# tiny84RGB.net
KiCad netlist of a schematic drawn in EAGLE
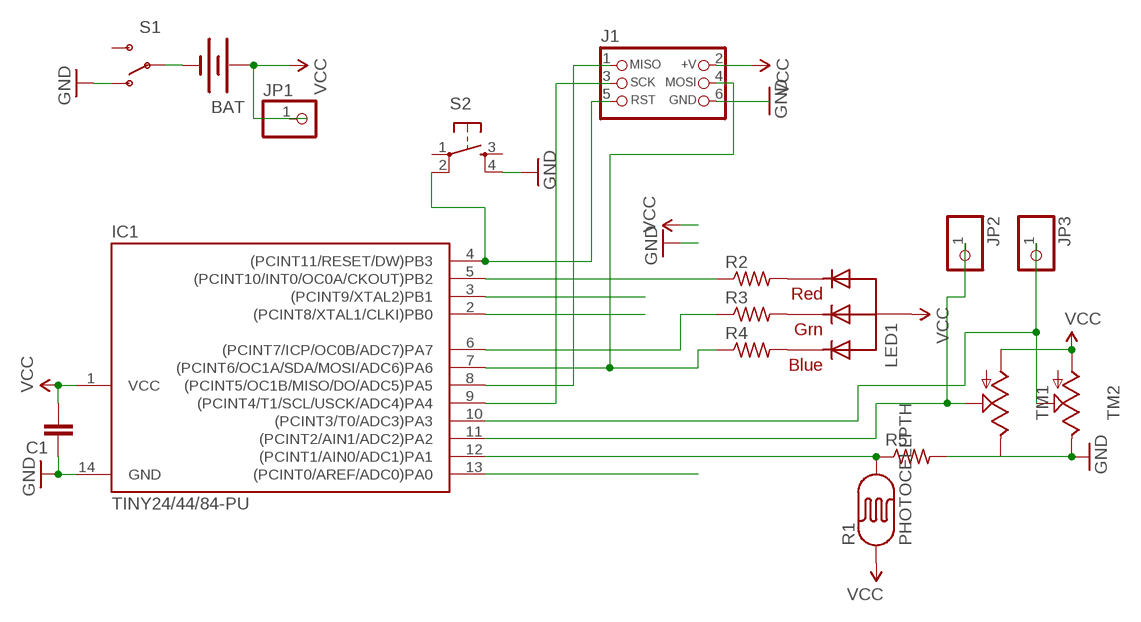
[diagram p0: schematic, sheet 1]

(export (version "E")
  (design (tool "Eeschema 10.0.6"))
  (components
    (comp (ref "BAT")
      (value "BATTERY20PTH")
      (footprint "eagle-import:BATTCOM_20MM_PTH")
      (libsource (lib "eagle-import") (part "BATTERY20PTH"))
    )
    (comp (ref "C1")
      (value "CAPKIT")
      (footprint "eagle-import:CAP-PTH-SMALL-KIT")
      (libsource (lib "eagle-import") (part "CAPKIT"))
    )
    (comp (ref "IC1")
      (value "TINY24/44/84-PU")
      (footprint "eagle-import:DIL14")
      (libsource (lib "eagle-import") (part "TINY24/44/84-PU"))
    )
    (comp (ref "J1")
      (value "CON_HEADER_PRG_AVR_ICSP-PTH")
      (footprint "eagle-import:HEADER_PRG_2X03")
      (libsource (lib "eagle-import") (part "CON_HEADER_PRG_AVR_ICSP-PTH"))
    )
    (comp (ref "JP1")
      (value "PINHD-1X1CB")
      (footprint "eagle-import:1X01-CLEANBIG")
      (libsource (lib "eagle-import") (part "PINHD-1X1CB"))
    )
    (comp (ref "JP2")
      (value "PINHD-1X1CB")
      (footprint "eagle-import:1X01-CLEANBIG")
      (libsource (lib "eagle-import") (part "PINHD-1X1CB"))
    )
    (comp (ref "JP3")
      (value "PINHD-1X1CB")
      (footprint "eagle-import:1X01-CLEANBIG")
      (libsource (lib "eagle-import") (part "PINHD-1X1CB"))
    )
    (comp (ref "LED1")
      (value "RGBLED_CA-5MM")
      (footprint "eagle-import:LED5MMRGB")
      (libsource (lib "eagle-import") (part "RGBLED_CA-5MM"))
    )
    (comp (ref "R1")
      (value "PHOTOCELLPTH")
      (footprint "eagle-import:PHOTOCELL")
      (libsource (lib "eagle-import") (part "PHOTOCELLPTH"))
    )
    (comp (ref "R2")
      (value "R-US_0204/7")
      (footprint "eagle-import:0204_7")
      (libsource (lib "eagle-import") (part "R-US_0204/7"))
    )
    (comp (ref "R3")
      (value "R-US_0204/7")
      (footprint "eagle-import:0204_7")
      (libsource (lib "eagle-import") (part "R-US_0204/7"))
    )
    (comp (ref "R4")
      (value "R-US_0204/7")
      (footprint "eagle-import:0204_7")
      (libsource (lib "eagle-import") (part "R-US_0204/7"))
    )
    (comp (ref "R5")
      (value "R-US_0204/7")
      (footprint "eagle-import:0204_7")
      (libsource (lib "eagle-import") (part "R-US_0204/7"))
    )
    (comp (ref "S1")
      (value "SWITCH-SPSTPTH")
      (footprint "eagle-import:SWITCH-SPDT")
      (libsource (lib "eagle-import") (part "SWITCH-SPSTPTH"))
    )
    (comp (ref "S2")
      (value "TAC_SWITCHPTH")
      (footprint "eagle-import:TACTILE-PTH")
      (libsource (lib "eagle-import") (part "TAC_SWITCHPTH"))
    )
    (comp (ref "TM1")
      (value "TRIM")
      (footprint "eagle-import:6MM")
      (libsource (lib "eagle-import") (part "TRIM"))
    )
    (comp (ref "TM2")
      (value "TRIM")
      (footprint "eagle-import:6MM")
      (libsource (lib "eagle-import") (part "TRIM"))
    )
  )
  (nets
    (net (code "1") (name "GND") (class "Default")
      (node (ref "C1") (pin "1") (pinfunction "1_1") (pintype "passive"))
      (node (ref "IC1") (pin "14") (pinfunction "GND_14") (pintype "power_in"))
      (node (ref "R5") (pin "2") (pinfunction "2_2") (pintype "passive"))
      (node (ref "S1") (pin "1") (pinfunction "O_1") (pintype "passive"))
      (node (ref "S2") (pin "4") (pinfunction "4_4") (pintype "passive"))
      (node (ref "TM1") (pin "E") (pinfunction "E_E") (pintype "passive"))
      (node (ref "TM2") (pin "E") (pinfunction "E_E") (pintype "passive"))
    )
    (net (code "2") (name "Net-(BAT--)") (class "Default")
      (node (ref "BAT") (pin "2") (pinfunction "-_2") (pintype "power_in"))
      (node (ref "S1") (pin "2") (pinfunction "P_2") (pintype "passive"))
    )
    (net (code "3") (name "Net-(IC1-(PCINT1{slash}AIN0{slash}ADC1)PA1)") (class "Default")
      (node (ref "IC1") (pin "12") (pinfunction "(PCINT1/AIN0/ADC1)PA1_12") (pintype "bidirectional"))
      (node (ref "R1") (pin "2") (pinfunction "P$2_2") (pintype "bidirectional"))
      (node (ref "R5") (pin "1") (pinfunction "1_1") (pintype "passive"))
    )
    (net (code "4") (name "Net-(IC1-(PCINT2{slash}AIN1{slash}ADC2)PA2)") (class "Default")
      (node (ref "IC1") (pin "11") (pinfunction "(PCINT2/AIN1/ADC2)PA2_11") (pintype "bidirectional"))
      (node (ref "JP2") (pin "1") (pinfunction "1_1") (pintype "passive"))
      (node (ref "TM1") (pin "S") (pinfunction "S_S") (pintype "passive"))
    )
    (net (code "5") (name "Net-(IC1-(PCINT3{slash}T0{slash}ADC3)PA3)") (class "Default")
      (node (ref "IC1") (pin "10") (pinfunction "(PCINT3/T0/ADC3)PA3_10") (pintype "bidirectional"))
      (node (ref "JP3") (pin "1") (pinfunction "1_1") (pintype "passive"))
      (node (ref "TM2") (pin "S") (pinfunction "S_S") (pintype "passive"))
    )
    (net (code "6") (name "Net-(IC1-(PCINT4{slash}T1{slash}SCL{slash}USCK{slash}ADC4)PA4)") (class "Default")
      (node (ref "IC1") (pin "9") (pinfunction "(PCINT4/T1/SCL/USCK/ADC4)PA4_9") (pintype "bidirectional"))
      (node (ref "J1") (pin "3") (pinfunction "SCK_3") (pintype "passive"))
    )
    (net (code "7") (name "Net-(IC1-(PCINT5{slash}OC1B{slash}MISO{slash}DO{slash}ADC5)PA5)") (class "Default")
      (node (ref "IC1") (pin "8") (pinfunction "(PCINT5/OC1B/MISO/DO/ADC5)PA5_8") (pintype "bidirectional"))
      (node (ref "J1") (pin "1") (pinfunction "MISO_1") (pintype "passive"))
    )
    (net (code "8") (name "Net-(IC1-(PCINT6{slash}OC1A{slash}SDA{slash}MOSI{slash}ADC6)PA6)") (class "Default")
      (node (ref "IC1") (pin "7") (pinfunction "(PCINT6/OC1A/SDA/MOSI/ADC6)PA6_7") (pintype "bidirectional"))
      (node (ref "J1") (pin "4") (pinfunction "MOSI_4") (pintype "passive"))
      (node (ref "R4") (pin "1") (pinfunction "1_1") (pintype "passive"))
    )
    (net (code "9") (name "Net-(IC1-(PCINT7{slash}ICP{slash}OC0B{slash}ADC7)PA7)") (class "Default")
      (node (ref "IC1") (pin "6") (pinfunction "(PCINT7/ICP/OC0B/ADC7)PA7_6") (pintype "bidirectional"))
      (node (ref "R3") (pin "1") (pinfunction "1_1") (pintype "passive"))
    )
    (net (code "10") (name "Net-(IC1-(PCINT10{slash}INT0{slash}OC0A{slash}CKOUT)PB2)") (class "Default")
      (node (ref "IC1") (pin "5") (pinfunction "(PCINT10/INT0/OC0A/CKOUT)PB2_5") (pintype "bidirectional"))
      (node (ref "R2") (pin "1") (pinfunction "1_1") (pintype "passive"))
    )
    (net (code "11") (name "Net-(IC1-(PCINT11{slash}RESET{slash}DW)PB3)") (class "Default")
      (node (ref "IC1") (pin "4") (pinfunction "(PCINT11/RESET/DW)PB3_4") (pintype "bidirectional"))
      (node (ref "J1") (pin "5") (pinfunction "RST_5") (pintype "passive"))
      (node (ref "S2") (pin "2") (pinfunction "2_2") (pintype "passive"))
    )
    (net (code "12") (name "Net-(LED1-BLUE)") (class "Default")
      (node (ref "LED1") (pin "4") (pinfunction "BLUE_4") (pintype "bidirectional"))
      (node (ref "R4") (pin "2") (pinfunction "2_2") (pintype "passive"))
    )
    (net (code "13") (name "Net-(LED1-GREEN)") (class "Default")
      (node (ref "LED1") (pin "3") (pinfunction "GREEN_3") (pintype "bidirectional"))
      (node (ref "R3") (pin "2") (pinfunction "2_2") (pintype "passive"))
    )
    (net (code "14") (name "Net-(LED1-RED)") (class "Default")
      (node (ref "LED1") (pin "1") (pinfunction "RED_1") (pintype "bidirectional"))
      (node (ref "R2") (pin "2") (pinfunction "2_2") (pintype "passive"))
    )
    (net (code "15") (name "VCC") (class "Default")
      (node (ref "BAT") (pin "1") (pinfunction "+_1") (pintype "power_in"))
      (node (ref "C1") (pin "2") (pinfunction "2_2") (pintype "passive"))
      (node (ref "IC1") (pin "1") (pinfunction "VCC_1") (pintype "power_in"))
      (node (ref "J1") (pin "2") (pinfunction "+V_2") (pintype "passive"))
      (node (ref "JP1") (pin "1") (pinfunction "1_1") (pintype "passive"))
      (node (ref "LED1") (pin "2") (pinfunction "VCC_2") (pintype "bidirectional"))
      (node (ref "R1") (pin "1") (pinfunction "P$1_1") (pintype "bidirectional"))
      (node (ref "TM1") (pin "A") (pinfunction "A_A") (pintype "passive"))
      (node (ref "TM2") (pin "A") (pinfunction "A_A") (pintype "passive"))
    )
    (net (code "16") (name "unconnected-(IC1-(PCINT0{slash}AREF{slash}ADC0)PA0-Pad13)") (class "Default")
      (node (ref "IC1") (pin "13") (pinfunction "(PCINT0/AREF/ADC0)PA0_13") (pintype "bidirectional"))
    )
    (net (code "17") (name "unconnected-(IC1-(PCINT8{slash}XTAL1{slash}CLKI)PB0-Pad2)") (class "Default")
      (node (ref "IC1") (pin "2") (pinfunction "(PCINT8/XTAL1/CLKI)PB0_2") (pintype "bidirectional"))
    )
    (net (code "18") (name "unconnected-(IC1-(PCINT9{slash}XTAL2)PB1-Pad3)") (class "Default")
      (node (ref "IC1") (pin "3") (pinfunction "(PCINT9/XTAL2)PB1_3") (pintype "bidirectional"))
    )
    (net (code "19") (name "unconnected-(J1-GND-Pad6)") (class "Default")
      (node (ref "J1") (pin "6") (pinfunction "GND_6") (pintype "passive"))
    )
    (net (code "20") (name "unconnected-(S1-S-Pad3)") (class "Default")
      (node (ref "S1") (pin "3") (pinfunction "S_3") (pintype "passive"))
    )
    (net (code "21") (name "unconnected-(S2-Pad1)") (class "Default")
      (node (ref "S2") (pin "1") (pinfunction "1_1") (pintype "passive"))
    )
    (net (code "22") (name "unconnected-(S2-Pad3)") (class "Default")
      (node (ref "S2") (pin "3") (pinfunction "3_3") (pintype "passive"))
    )
  )
)
